# RasPiDV.net
KiCad netlist of a schematic drawn in EAGLE
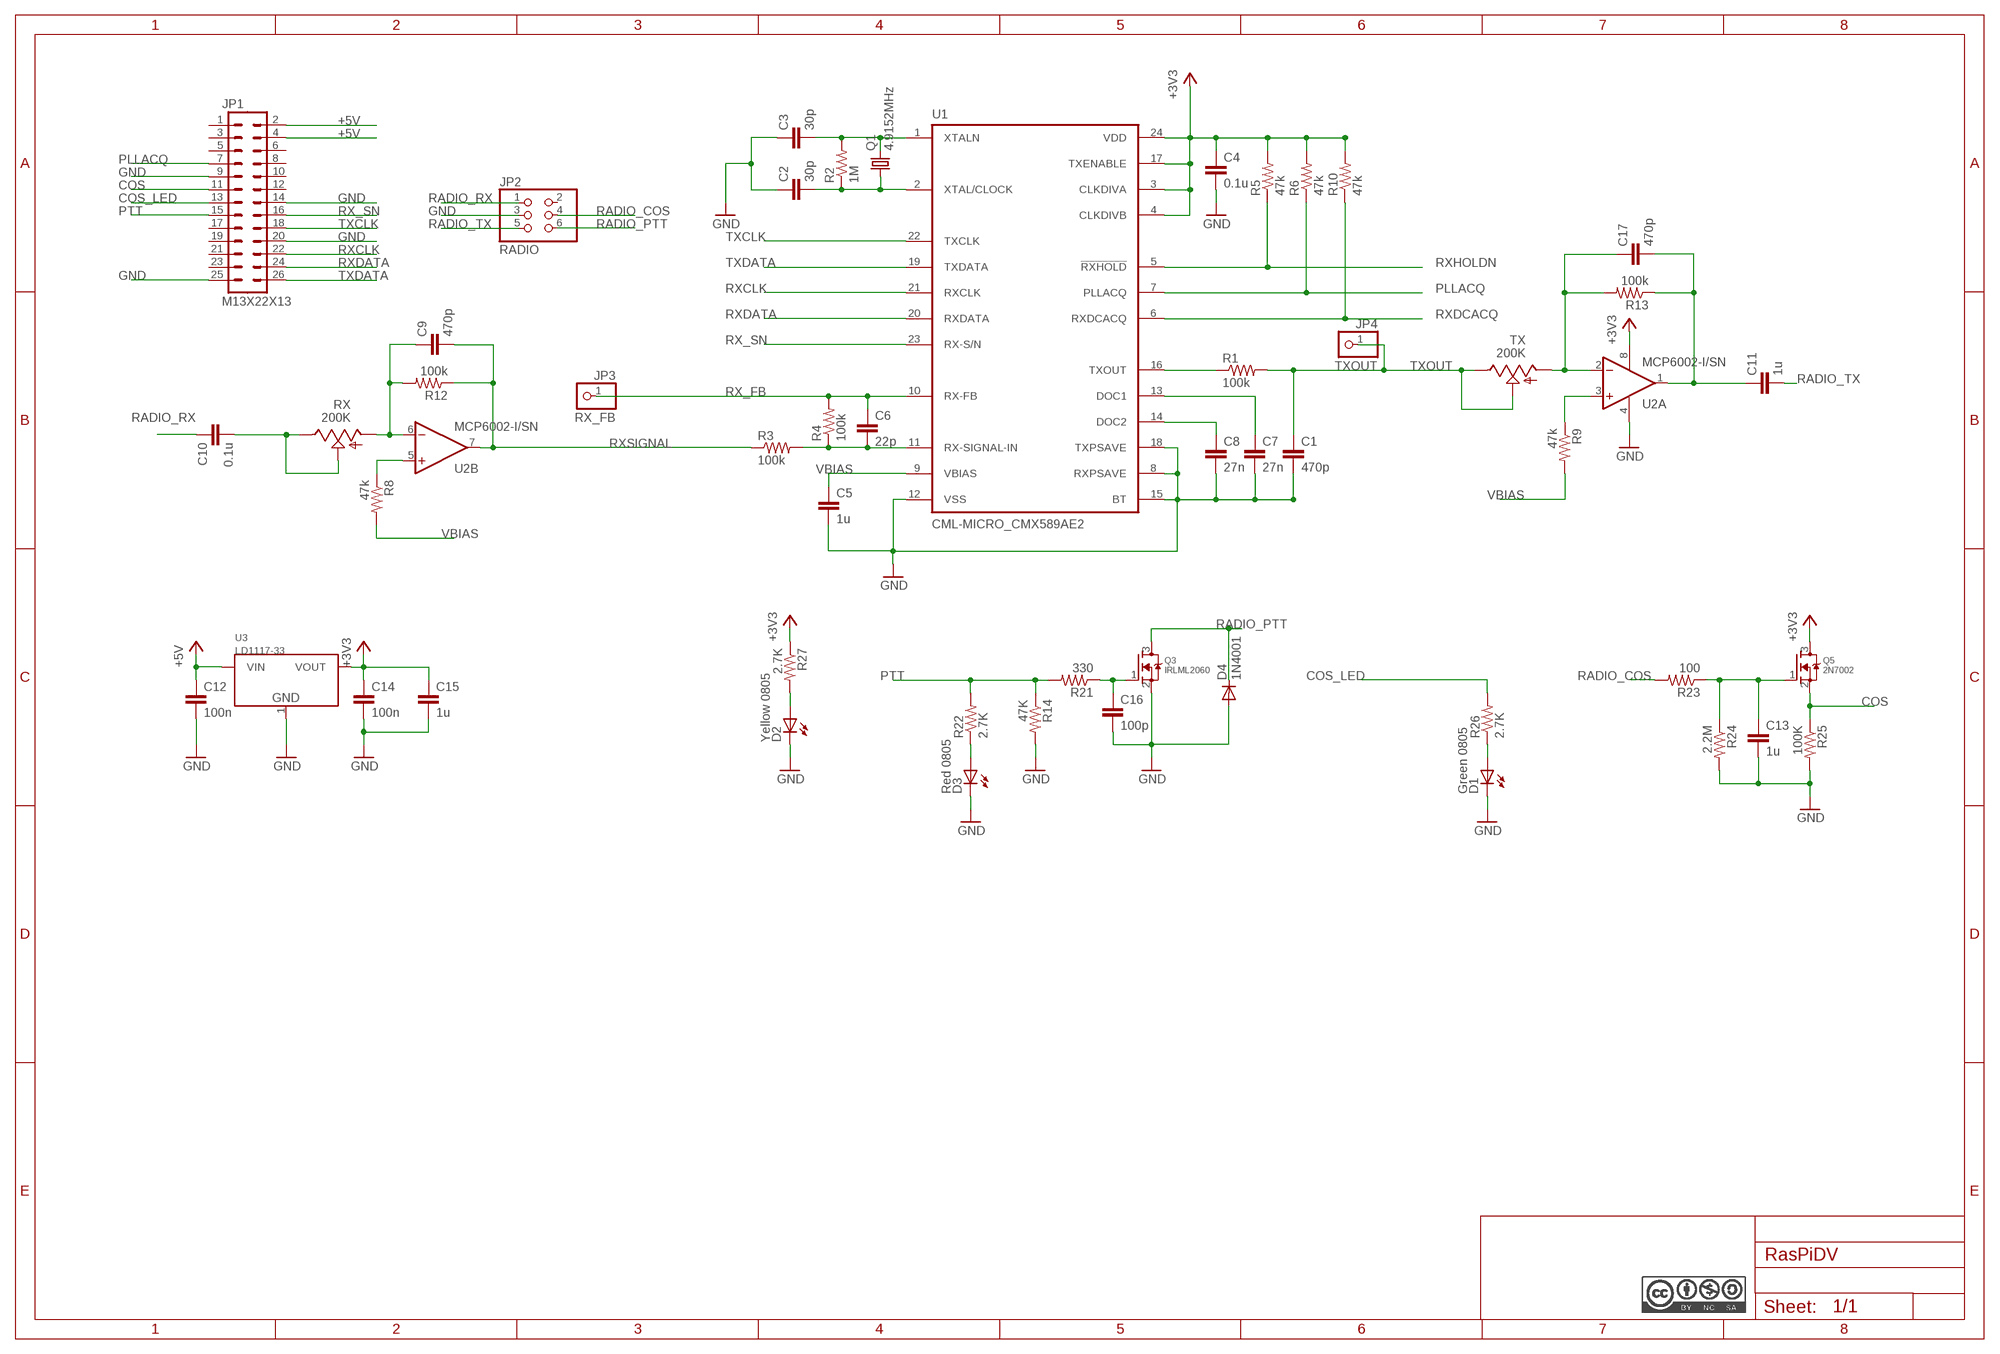
[diagram p0: schematic, sheet 1]

(export (version "E")
  (design (tool "Eeschema 10.0.6"))
  (components
    (comp (ref "C1")
      (value "470p")
      (footprint "eagle-import:C0805")
      (libsource (lib "eagle-import") (part "C-EUC0805"))
    )
    (comp (ref "C2")
      (value "30p")
      (footprint "eagle-import:C0805")
      (libsource (lib "eagle-import") (part "C-EUC0805"))
    )
    (comp (ref "C3")
      (value "30p")
      (footprint "eagle-import:C0805")
      (libsource (lib "eagle-import") (part "C-EUC0805"))
    )
    (comp (ref "C4")
      (value "0.1u")
      (footprint "eagle-import:C0805")
      (libsource (lib "eagle-import") (part "C-EUC0805"))
    )
    (comp (ref "C5")
      (value "1u")
      (footprint "eagle-import:C0805")
      (libsource (lib "eagle-import") (part "C-EUC0805"))
    )
    (comp (ref "C6")
      (value "22p")
      (footprint "eagle-import:C0805")
      (libsource (lib "eagle-import") (part "C-EUC0805"))
    )
    (comp (ref "C7")
      (value "27n")
      (footprint "eagle-import:C0805")
      (libsource (lib "eagle-import") (part "C-EUC0805"))
    )
    (comp (ref "C8")
      (value "27n")
      (footprint "eagle-import:C0805")
      (libsource (lib "eagle-import") (part "C-EUC0805"))
    )
    (comp (ref "C9")
      (value "470p")
      (footprint "eagle-import:C0805")
      (libsource (lib "eagle-import") (part "C-EUC0805"))
    )
    (comp (ref "C10")
      (value "0.1u")
      (footprint "eagle-import:C0805")
      (libsource (lib "eagle-import") (part "C-EUC0805"))
    )
    (comp (ref "C11")
      (value "1u")
      (footprint "eagle-import:C0805")
      (libsource (lib "eagle-import") (part "C-EUC0805"))
    )
    (comp (ref "C12")
      (value "100n")
      (footprint "eagle-import:C0805")
      (libsource (lib "eagle-import") (part "C-EUC0805"))
    )
    (comp (ref "C13")
      (value "1u")
      (footprint "eagle-import:C0805")
      (libsource (lib "eagle-import") (part "C-EUC0805"))
    )
    (comp (ref "C14")
      (value "100n")
      (footprint "eagle-import:C0805")
      (libsource (lib "eagle-import") (part "C-EUC0805"))
    )
    (comp (ref "C15")
      (value "1u")
      (footprint "eagle-import:C0805")
      (libsource (lib "eagle-import") (part "C-EUC0805"))
    )
    (comp (ref "C16")
      (value "100p")
      (footprint "eagle-import:C0805")
      (libsource (lib "eagle-import") (part "C-EUC0805"))
    )
    (comp (ref "C17")
      (value "470p")
      (footprint "eagle-import:C0805")
      (libsource (lib "eagle-import") (part "C-EUC0805"))
    )
    (comp (ref "D1")
      (value "Green 0805")
      (footprint "eagle-import:CHIPLED_0805")
      (libsource (lib "eagle-import") (part "LEDCHIPLED_0805"))
    )
    (comp (ref "D2")
      (value "Yellow 0805")
      (footprint "eagle-import:CHIPLED_0805")
      (libsource (lib "eagle-import") (part "LEDCHIPLED_0805"))
    )
    (comp (ref "D3")
      (value "Red 0805")
      (footprint "eagle-import:CHIPLED_0805")
      (libsource (lib "eagle-import") (part "LEDCHIPLED_0805"))
    )
    (comp (ref "D4")
      (value "1N4001")
      (footprint "eagle-import:MICROMELF-R")
      (libsource (lib "eagle-import") (part "DIODE-MICROMELF-R"))
    )
    (comp (ref "JP1")
      (value "M13X22X13")
      (footprint "eagle-import:2X13")
      (libsource (lib "eagle-import") (part "M13X22X13"))
    )
    (comp (ref "JP2")
      (value "RADIO")
      (footprint "eagle-import:2X03_ROUND_70MIL")
      (libsource (lib "eagle-import") (part "HEADER-2X3"))
    )
    (comp (ref "JP3")
      (value "RX_FB")
      (footprint "eagle-import:1X01_ROUND")
      (libsource (lib "eagle-import") (part "HEADER-1X1ROUND"))
    )
    (comp (ref "JP4")
      (value "TXOUT")
      (footprint "eagle-import:1X01_ROUND")
      (libsource (lib "eagle-import") (part "HEADER-1X1ROUND"))
    )
    (comp (ref "Q1")
      (value "4.9152MHz")
      (footprint "eagle-import:CRYSTAL_HC49_S")
      (libsource (lib "eagle-import") (part "CRYSTAL_CRYSTALHC49S"))
    )
    (comp (ref "Q3")
      (value "IRLML2060")
      (footprint "eagle-import:SOT23")
      (libsource (lib "eagle-import") (part "MOSFET-NREFLOW"))
    )
    (comp (ref "Q5")
      (value "2N7002")
      (footprint "eagle-import:SOT23-R")
      (libsource (lib "eagle-import") (part "microbuilder_MOSFET-NREFLOW"))
    )
    (comp (ref "R1")
      (value "100k")
      (footprint "eagle-import:R0805W")
      (libsource (lib "eagle-import") (part "R-US_R0805W"))
    )
    (comp (ref "R2")
      (value "1M")
      (footprint "eagle-import:R0805W")
      (libsource (lib "eagle-import") (part "R-US_R0805W"))
    )
    (comp (ref "R3")
      (value "100k")
      (footprint "eagle-import:R0805W")
      (libsource (lib "eagle-import") (part "R-US_R0805W"))
    )
    (comp (ref "R4")
      (value "100k")
      (footprint "eagle-import:R0805W")
      (libsource (lib "eagle-import") (part "R-US_R0805W"))
    )
    (comp (ref "R5")
      (value "47k")
      (footprint "eagle-import:R0805W")
      (libsource (lib "eagle-import") (part "R-US_R0805W"))
    )
    (comp (ref "R6")
      (value "47k")
      (footprint "eagle-import:R0805W")
      (libsource (lib "eagle-import") (part "R-US_R0805W"))
    )
    (comp (ref "R8")
      (value "47k")
      (footprint "eagle-import:R0805W")
      (libsource (lib "eagle-import") (part "R-US_R0805W"))
    )
    (comp (ref "R9")
      (value "47k")
      (footprint "eagle-import:R0805W")
      (libsource (lib "eagle-import") (part "R-US_R0805W"))
    )
    (comp (ref "R10")
      (value "47k")
      (footprint "eagle-import:R0805W")
      (libsource (lib "eagle-import") (part "R-US_R0805W"))
    )
    (comp (ref "R12")
      (value "100k")
      (footprint "eagle-import:R0805W")
      (libsource (lib "eagle-import") (part "R-US_R0805W"))
    )
    (comp (ref "R13")
      (value "100k")
      (footprint "eagle-import:R0805W")
      (libsource (lib "eagle-import") (part "R-US_R0805W"))
    )
    (comp (ref "R14")
      (value "47K")
      (footprint "eagle-import:R0805W")
      (libsource (lib "eagle-import") (part "R-US_R0805W"))
    )
    (comp (ref "R21")
      (value "330")
      (footprint "eagle-import:R0805W")
      (libsource (lib "eagle-import") (part "R-US_R0805W"))
    )
    (comp (ref "R22")
      (value "2.7K")
      (footprint "eagle-import:R0805W")
      (libsource (lib "eagle-import") (part "R-US_R0805W"))
    )
    (comp (ref "R23")
      (value "100")
      (footprint "eagle-import:R0805W")
      (libsource (lib "eagle-import") (part "R-US_R0805W"))
    )
    (comp (ref "R24")
      (value "2.2M")
      (footprint "eagle-import:R0805W")
      (libsource (lib "eagle-import") (part "R-US_R0805W"))
    )
    (comp (ref "R25")
      (value "100K")
      (footprint "eagle-import:R0805W")
      (libsource (lib "eagle-import") (part "R-US_R0805W"))
    )
    (comp (ref "R26")
      (value "2.7K")
      (footprint "eagle-import:R0805W")
      (libsource (lib "eagle-import") (part "R-US_R0805W"))
    )
    (comp (ref "R27")
      (value "2.7K")
      (footprint "eagle-import:R0805W")
      (libsource (lib "eagle-import") (part "R-US_R0805W"))
    )
    (comp (ref "RX")
      (value "200K")
      (footprint "eagle-import:B25P")
      (libsource (lib "eagle-import") (part "TRIM_US-B25P"))
    )
    (comp (ref "TX")
      (value "200K")
      (footprint "eagle-import:B25P")
      (libsource (lib "eagle-import") (part "TRIM_US-B25P"))
    )
    (comp (ref "U1")
      (value "CML-MICRO_CMX589AE2")
      (footprint "eagle-import:AIS_MK2_CML-MICRO_TSSOP24")
      (libsource (lib "eagle-import") (part "AIS_MK2_CML-MICRO_CMX589AE2"))
    )
    (comp (ref "U2")
      (value "MCP6002-I/SN")
      (footprint "eagle-import:SOIC-8")
      (libsource (lib "eagle-import") (part "MCP6002-I/SN"))
    )
    (comp (ref "U3")
      (value "LD1117-33")
      (footprint "eagle-import:SOT223")
      (libsource (lib "eagle-import") (part "LD1117-3.3SOT223"))
    )
  )
  (nets
    (net (code "1") (name "+3V3") (class "Default")
      (node (ref "C14") (pin "1") (pinfunction "1_1") (pintype "passive"))
      (node (ref "C15") (pin "1") (pinfunction "1_1") (pintype "passive"))
      (node (ref "C4") (pin "1") (pinfunction "1_1") (pintype "passive"))
      (node (ref "Q5") (pin "3") (pinfunction "D_3") (pintype "bidirectional"))
      (node (ref "R10") (pin "2") (pinfunction "2_2") (pintype "passive"))
      (node (ref "R27") (pin "1") (pinfunction "1_1") (pintype "passive"))
      (node (ref "R5") (pin "2") (pinfunction "2_2") (pintype "passive"))
      (node (ref "R6") (pin "2") (pinfunction "2_2") (pintype "passive"))
      (node (ref "U1") (pin "17") (pinfunction "TXENABLE_17") (pintype "input"))
      (node (ref "U1") (pin "24") (pinfunction "VDD_24") (pintype "power_in"))
      (node (ref "U1") (pin "3") (pinfunction "CLKDIVA_3") (pintype "input"))
      (node (ref "U1") (pin "4") (pinfunction "CLKDIVB_4") (pintype "input"))
      (node (ref "U2") (pin "8") (pinfunction "V+_8") (pintype "power_in"))
      (node (ref "U3") (pin "2") (pinfunction "VOUT_2") (pintype "bidirectional"))
    )
    (net (code "2") (name "+5V") (class "Default")
      (node (ref "C12") (pin "1") (pinfunction "1_1") (pintype "passive"))
      (node (ref "JP1") (pin "2") (pinfunction "2_2") (pintype "passive"))
      (node (ref "JP1") (pin "4") (pinfunction "4_4") (pintype "passive"))
      (node (ref "U3") (pin "3") (pinfunction "VIN_3") (pintype "bidirectional"))
    )
    (net (code "3") (name "/COS") (class "Default")
      (node (ref "JP1") (pin "11") (pinfunction "11_11") (pintype "passive"))
      (node (ref "Q5") (pin "2") (pinfunction "S_2") (pintype "bidirectional"))
      (node (ref "R25") (pin "1") (pinfunction "1_1") (pintype "passive"))
    )
    (net (code "4") (name "/COS_LED") (class "Default")
      (node (ref "JP1") (pin "13") (pinfunction "13_13") (pintype "passive"))
      (node (ref "R26") (pin "2") (pinfunction "2_2") (pintype "passive"))
    )
    (net (code "5") (name "/PLLACQ") (class "Default")
      (node (ref "JP1") (pin "7") (pinfunction "7_7") (pintype "passive"))
      (node (ref "R6") (pin "1") (pinfunction "1_1") (pintype "passive"))
      (node (ref "U1") (pin "7") (pinfunction "PLLACQ_7") (pintype "input"))
    )
    (net (code "6") (name "/PTT") (class "Default")
      (node (ref "JP1") (pin "15") (pinfunction "15_15") (pintype "passive"))
      (node (ref "R14") (pin "1") (pinfunction "1_1") (pintype "passive"))
      (node (ref "R21") (pin "2") (pinfunction "2_2") (pintype "passive"))
      (node (ref "R22") (pin "2") (pinfunction "2_2") (pintype "passive"))
    )
    (net (code "7") (name "/RADIO_COS") (class "Default")
      (node (ref "JP2") (pin "4") (pinfunction "4_4") (pintype "passive"))
      (node (ref "R23") (pin "2") (pinfunction "2_2") (pintype "passive"))
    )
    (net (code "8") (name "/RADIO_PTT") (class "Default")
      (node (ref "D4") (pin "C") (pinfunction "C_C") (pintype "passive"))
      (node (ref "JP2") (pin "6") (pinfunction "6_6") (pintype "passive"))
      (node (ref "Q3") (pin "3") (pinfunction "D_3") (pintype "bidirectional"))
    )
    (net (code "9") (name "/RADIO_RX") (class "Default")
      (node (ref "C10") (pin "1") (pinfunction "1_1") (pintype "passive"))
      (node (ref "JP2") (pin "1") (pinfunction "1_1") (pintype "passive"))
    )
    (net (code "10") (name "/RADIO_TX") (class "Default")
      (node (ref "C11") (pin "2") (pinfunction "2_2") (pintype "passive"))
      (node (ref "JP2") (pin "5") (pinfunction "5_5") (pintype "passive"))
    )
    (net (code "11") (name "/RXCLK") (class "Default")
      (node (ref "JP1") (pin "22") (pinfunction "22_22") (pintype "passive"))
      (node (ref "U1") (pin "21") (pinfunction "RXCLK_21") (pintype "output"))
    )
    (net (code "12") (name "/RXDATA") (class "Default")
      (node (ref "JP1") (pin "24") (pinfunction "24_24") (pintype "passive"))
      (node (ref "U1") (pin "20") (pinfunction "RXDATA_20") (pintype "output"))
    )
    (net (code "13") (name "/RXDCACQ") (class "Default")
      (node (ref "R10") (pin "1") (pinfunction "1_1") (pintype "passive"))
      (node (ref "U1") (pin "6") (pinfunction "RXDCACQ_6") (pintype "input"))
    )
    (net (code "14") (name "/RXHOLDN") (class "Default")
      (node (ref "R5") (pin "1") (pinfunction "1_1") (pintype "passive"))
      (node (ref "U1") (pin "5") (pinfunction "~{RXHOLD}_5") (pintype "input"))
    )
    (net (code "15") (name "/RXSIGNAL") (class "Default")
      (node (ref "C9") (pin "2") (pinfunction "2_2") (pintype "passive"))
      (node (ref "R12") (pin "1") (pinfunction "1_1") (pintype "passive"))
      (node (ref "R3") (pin "1") (pinfunction "1_1") (pintype "passive"))
      (node (ref "U2") (pin "7") (pinfunction "OUT_7") (pintype "output"))
    )
    (net (code "16") (name "/RX_FB") (class "Default")
      (node (ref "C6") (pin "1") (pinfunction "1_1") (pintype "passive"))
      (node (ref "JP3") (pin "1") (pinfunction "1_1") (pintype "passive"))
      (node (ref "R4") (pin "2") (pinfunction "2_2") (pintype "passive"))
      (node (ref "U1") (pin "10") (pinfunction "RX-FB_10") (pintype "input"))
    )
    (net (code "17") (name "/RX_SN") (class "Default")
      (node (ref "JP1") (pin "16") (pinfunction "16_16") (pintype "passive"))
      (node (ref "U1") (pin "23") (pinfunction "RX-S/N_23") (pintype "output"))
    )
    (net (code "18") (name "/TXCLK") (class "Default")
      (node (ref "JP1") (pin "18") (pinfunction "18_18") (pintype "passive"))
      (node (ref "U1") (pin "22") (pinfunction "TXCLK_22") (pintype "output"))
    )
    (net (code "19") (name "/TXDATA") (class "Default")
      (node (ref "JP1") (pin "26") (pinfunction "26_26") (pintype "passive"))
      (node (ref "U1") (pin "19") (pinfunction "TXDATA_19") (pintype "input"))
    )
    (net (code "20") (name "/TXOUT") (class "Default")
      (node (ref "C1") (pin "1") (pinfunction "1_1") (pintype "passive"))
      (node (ref "JP4") (pin "1") (pinfunction "1_1") (pintype "passive"))
      (node (ref "R1") (pin "2") (pinfunction "2_2") (pintype "passive"))
      (node (ref "TX") (pin "E") (pinfunction "E_E") (pintype "passive"))
      (node (ref "TX") (pin "S") (pinfunction "S_S") (pintype "passive"))
    )
    (net (code "21") (name "/VBIAS") (class "Default")
      (node (ref "C5") (pin "1") (pinfunction "1_1") (pintype "passive"))
      (node (ref "R8") (pin "2") (pinfunction "2_2") (pintype "passive"))
      (node (ref "R9") (pin "2") (pinfunction "2_2") (pintype "passive"))
      (node (ref "U1") (pin "9") (pinfunction "VBIAS_9") (pintype "input"))
    )
    (net (code "22") (name "GND") (class "Default")
      (node (ref "C1") (pin "2") (pinfunction "2_2") (pintype "passive"))
      (node (ref "C12") (pin "2") (pinfunction "2_2") (pintype "passive"))
      (node (ref "C13") (pin "2") (pinfunction "2_2") (pintype "passive"))
      (node (ref "C14") (pin "2") (pinfunction "2_2") (pintype "passive"))
      (node (ref "C15") (pin "2") (pinfunction "2_2") (pintype "passive"))
      (node (ref "C16") (pin "2") (pinfunction "2_2") (pintype "passive"))
      (node (ref "C2") (pin "1") (pinfunction "1_1") (pintype "passive"))
      (node (ref "C3") (pin "1") (pinfunction "1_1") (pintype "passive"))
      (node (ref "C4") (pin "2") (pinfunction "2_2") (pintype "passive"))
      (node (ref "C5") (pin "2") (pinfunction "2_2") (pintype "passive"))
      (node (ref "C7") (pin "2") (pinfunction "2_2") (pintype "passive"))
      (node (ref "C8") (pin "2") (pinfunction "2_2") (pintype "passive"))
      (node (ref "D1") (pin "C") (pinfunction "C_C") (pintype "passive"))
      (node (ref "D2") (pin "C") (pinfunction "C_C") (pintype "passive"))
      (node (ref "D3") (pin "C") (pinfunction "C_C") (pintype "passive"))
      (node (ref "D4") (pin "A") (pinfunction "A_A") (pintype "passive"))
      (node (ref "JP1") (pin "14") (pinfunction "14_14") (pintype "passive"))
      (node (ref "JP1") (pin "20") (pinfunction "20_20") (pintype "passive"))
      (node (ref "JP1") (pin "25") (pinfunction "25_25") (pintype "passive"))
      (node (ref "JP1") (pin "9") (pinfunction "9_9") (pintype "passive"))
      (node (ref "JP2") (pin "3") (pinfunction "3_3") (pintype "passive"))
      (node (ref "Q3") (pin "2") (pinfunction "S_2") (pintype "bidirectional"))
      (node (ref "R14") (pin "2") (pinfunction "2_2") (pintype "passive"))
      (node (ref "R24") (pin "2") (pinfunction "2_2") (pintype "passive"))
      (node (ref "R25") (pin "2") (pinfunction "2_2") (pintype "passive"))
      (node (ref "U1") (pin "12") (pinfunction "VSS_12") (pintype "power_in"))
      (node (ref "U1") (pin "15") (pinfunction "BT_15") (pintype "input"))
      (node (ref "U1") (pin "18") (pinfunction "TXPSAVE_18") (pintype "input"))
      (node (ref "U1") (pin "8") (pinfunction "RXPSAVE_8") (pintype "input"))
      (node (ref "U2") (pin "4") (pinfunction "V-_4") (pintype "power_in"))
      (node (ref "U3") (pin "1") (pinfunction "GND_1") (pintype "bidirectional"))
    )
    (net (code "23") (name "Net-(C10-Pad2)") (class "Default")
      (node (ref "C10") (pin "2") (pinfunction "2_2") (pintype "passive"))
      (node (ref "RX") (pin "E") (pinfunction "E_E") (pintype "passive"))
      (node (ref "RX") (pin "S") (pinfunction "S_S") (pintype "passive"))
    )
    (net (code "24") (name "Net-(D1-PadA)") (class "Default")
      (node (ref "D1") (pin "A") (pinfunction "A_A") (pintype "passive"))
      (node (ref "R26") (pin "1") (pinfunction "1_1") (pintype "passive"))
    )
    (net (code "25") (name "Net-(D2-PadA)") (class "Default")
      (node (ref "D2") (pin "A") (pinfunction "A_A") (pintype "passive"))
      (node (ref "R27") (pin "2") (pinfunction "2_2") (pintype "passive"))
    )
    (net (code "26") (name "Net-(D3-PadA)") (class "Default")
      (node (ref "D3") (pin "A") (pinfunction "A_A") (pintype "passive"))
      (node (ref "R22") (pin "1") (pinfunction "1_1") (pintype "passive"))
    )
    (net (code "27") (name "Net-(Q3-G)") (class "Default")
      (node (ref "C16") (pin "1") (pinfunction "1_1") (pintype "passive"))
      (node (ref "Q3") (pin "1") (pinfunction "G_1") (pintype "bidirectional"))
      (node (ref "R21") (pin "1") (pinfunction "1_1") (pintype "passive"))
    )
    (net (code "28") (name "Net-(Q5-G)") (class "Default")
      (node (ref "C13") (pin "1") (pinfunction "1_1") (pintype "passive"))
      (node (ref "Q5") (pin "1") (pinfunction "G_1") (pintype "bidirectional"))
      (node (ref "R23") (pin "1") (pinfunction "1_1") (pintype "passive"))
      (node (ref "R24") (pin "1") (pinfunction "1_1") (pintype "passive"))
    )
    (net (code "29") (name "Net-(U1-DOC1)") (class "Default")
      (node (ref "C7") (pin "1") (pinfunction "1_1") (pintype "passive"))
      (node (ref "U1") (pin "13") (pinfunction "DOC1_13") (pintype "passive"))
    )
    (net (code "30") (name "Net-(U1-DOC2)") (class "Default")
      (node (ref "C8") (pin "1") (pinfunction "1_1") (pintype "passive"))
      (node (ref "U1") (pin "14") (pinfunction "DOC2_14") (pintype "passive"))
    )
    (net (code "31") (name "Net-(U1-RX-SIGNAL-IN)") (class "Default")
      (node (ref "C6") (pin "2") (pinfunction "2_2") (pintype "passive"))
      (node (ref "R3") (pin "2") (pinfunction "2_2") (pintype "passive"))
      (node (ref "R4") (pin "1") (pinfunction "1_1") (pintype "passive"))
      (node (ref "U1") (pin "11") (pinfunction "RX-SIGNAL-IN_11") (pintype "input"))
    )
    (net (code "32") (name "Net-(U1-TXOUT)") (class "Default")
      (node (ref "R1") (pin "1") (pinfunction "1_1") (pintype "passive"))
      (node (ref "U1") (pin "16") (pinfunction "TXOUT_16") (pintype "output"))
    )
    (net (code "33") (name "Net-(U1-XTALN)") (class "Default")
      (node (ref "C3") (pin "2") (pinfunction "2_2") (pintype "passive"))
      (node (ref "Q1") (pin "2") (pinfunction "2_2") (pintype "passive"))
      (node (ref "R2") (pin "2") (pinfunction "2_2") (pintype "passive"))
      (node (ref "U1") (pin "1") (pinfunction "XTALN_1") (pintype "output"))
    )
    (net (code "34") (name "Net-(U1-XTAL{slash}CLOCK)") (class "Default")
      (node (ref "C2") (pin "2") (pinfunction "2_2") (pintype "passive"))
      (node (ref "Q1") (pin "1") (pinfunction "1_1") (pintype "passive"))
      (node (ref "R2") (pin "1") (pinfunction "1_1") (pintype "passive"))
      (node (ref "U1") (pin "2") (pinfunction "XTAL/CLOCK_2") (pintype "input"))
    )
    (net (code "35") (name "Net-(U2A-IN+)") (class "Default")
      (node (ref "R9") (pin "1") (pinfunction "1_1") (pintype "passive"))
      (node (ref "U2") (pin "3") (pinfunction "IN+_3") (pintype "input"))
    )
    (net (code "36") (name "Net-(U2A-IN-)") (class "Default")
      (node (ref "C17") (pin "1") (pinfunction "1_1") (pintype "passive"))
      (node (ref "R13") (pin "2") (pinfunction "2_2") (pintype "passive"))
      (node (ref "TX") (pin "A") (pinfunction "A_A") (pintype "passive"))
      (node (ref "U2") (pin "2") (pinfunction "IN-_2") (pintype "input"))
    )
    (net (code "37") (name "Net-(U2A-OUT)") (class "Default")
      (node (ref "C11") (pin "1") (pinfunction "1_1") (pintype "passive"))
      (node (ref "C17") (pin "2") (pinfunction "2_2") (pintype "passive"))
      (node (ref "R13") (pin "1") (pinfunction "1_1") (pintype "passive"))
      (node (ref "U2") (pin "1") (pinfunction "OUT_1") (pintype "output"))
    )
    (net (code "38") (name "Net-(U2B-IN+)") (class "Default")
      (node (ref "R8") (pin "1") (pinfunction "1_1") (pintype "passive"))
      (node (ref "U2") (pin "5") (pinfunction "IN+_5") (pintype "input"))
    )
    (net (code "39") (name "Net-(U2B-IN-)") (class "Default")
      (node (ref "C9") (pin "1") (pinfunction "1_1") (pintype "passive"))
      (node (ref "R12") (pin "2") (pinfunction "2_2") (pintype "passive"))
      (node (ref "RX") (pin "A") (pinfunction "A_A") (pintype "passive"))
      (node (ref "U2") (pin "6") (pinfunction "IN-_6") (pintype "input"))
    )
    (net (code "40") (name "unconnected-(JP1-Pad1)") (class "Default")
      (node (ref "JP1") (pin "1") (pinfunction "1_1") (pintype "passive"))
    )
    (net (code "41") (name "unconnected-(JP1-Pad3)") (class "Default")
      (node (ref "JP1") (pin "3") (pinfunction "3_3") (pintype "passive"))
    )
    (net (code "42") (name "unconnected-(JP1-Pad5)") (class "Default")
      (node (ref "JP1") (pin "5") (pinfunction "5_5") (pintype "passive"))
    )
    (net (code "43") (name "unconnected-(JP1-Pad6)") (class "Default")
      (node (ref "JP1") (pin "6") (pinfunction "6_6") (pintype "passive"))
    )
    (net (code "44") (name "unconnected-(JP1-Pad8)") (class "Default")
      (node (ref "JP1") (pin "8") (pinfunction "8_8") (pintype "passive"))
    )
    (net (code "45") (name "unconnected-(JP1-Pad10)") (class "Default")
      (node (ref "JP1") (pin "10") (pinfunction "10_10") (pintype "passive"))
    )
    (net (code "46") (name "unconnected-(JP1-Pad12)") (class "Default")
      (node (ref "JP1") (pin "12") (pinfunction "12_12") (pintype "passive"))
    )
    (net (code "47") (name "unconnected-(JP1-Pad17)") (class "Default")
      (node (ref "JP1") (pin "17") (pinfunction "17_17") (pintype "passive"))
    )
    (net (code "48") (name "unconnected-(JP1-Pad19)") (class "Default")
      (node (ref "JP1") (pin "19") (pinfunction "19_19") (pintype "passive"))
    )
    (net (code "49") (name "unconnected-(JP1-Pad21)") (class "Default")
      (node (ref "JP1") (pin "21") (pinfunction "21_21") (pintype "passive"))
    )
    (net (code "50") (name "unconnected-(JP1-Pad23)") (class "Default")
      (node (ref "JP1") (pin "23") (pinfunction "23_23") (pintype "passive"))
    )
    (net (code "51") (name "unconnected-(JP2-Pad2)") (class "Default")
      (node (ref "JP2") (pin "2") (pinfunction "2_2") (pintype "passive"))
    )
  )
)
